# ProPrj_usb__2025-12-10-17-32-04.net
KiCad netlist of a schematic drawn in EasyEDA Pro
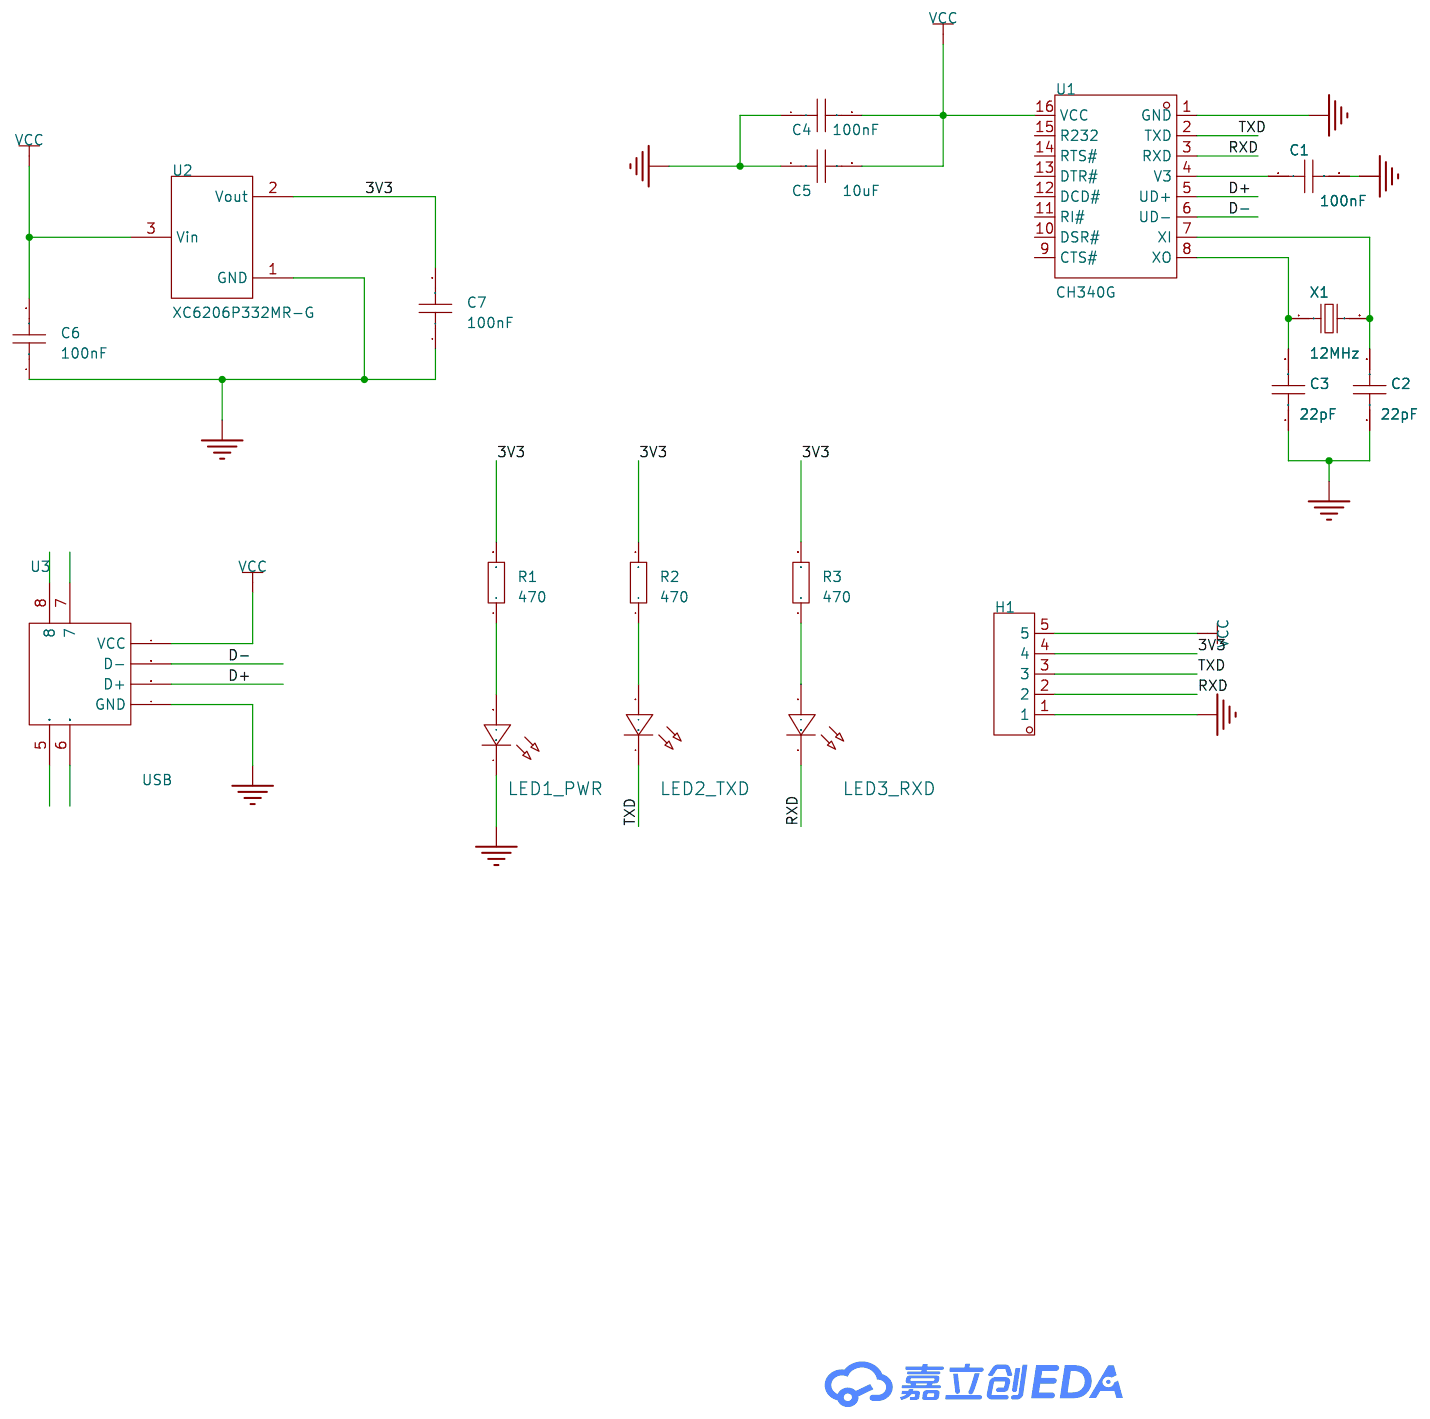
[diagram p0: schematic sheet]

(export (version "E")
  (design (tool "Eeschema 10.0.6"))
  (components
    (comp (ref "C1")
      (value "100nF")
      (footprint "easyedapro:C0603")
      (libsource (lib "easyedapro") (part "Capacitance"))
    )
    (comp (ref "C2")
      (value "22pF")
      (footprint "easyedapro:C0603")
      (libsource (lib "easyedapro") (part "Capacitance"))
    )
    (comp (ref "C3")
      (value "22pF")
      (footprint "easyedapro:C0603")
      (libsource (lib "easyedapro") (part "Capacitance"))
    )
    (comp (ref "C4")
      (value "100nF")
      (footprint "easyedapro:C0603")
      (libsource (lib "easyedapro") (part "Capacitance"))
    )
    (comp (ref "C5")
      (value "10uF")
      (footprint "easyedapro:C0603")
      (libsource (lib "easyedapro") (part "Capacitance"))
    )
    (comp (ref "C6")
      (value "100nF")
      (footprint "easyedapro:C0603")
      (libsource (lib "easyedapro") (part "Capacitance"))
    )
    (comp (ref "C7")
      (value "100nF")
      (footprint "easyedapro:C0603")
      (libsource (lib "easyedapro") (part "Capacitance"))
    )
    (comp (ref "H1")
      (value "~")
      (footprint "easyedapro:HDR-TH_5P-P2.54-V-M")
      (libsource (lib "easyedapro") (part "MTP125-1105S1"))
    )
    (comp (ref "LED1_PWR")
      (value "~")
      (footprint "easyedapro:LED_0603")
      (libsource (lib "easyedapro") (part "LED_R"))
    )
    (comp (ref "LED2_TXD")
      (value "~")
      (footprint "easyedapro:LED_0603")
      (libsource (lib "easyedapro") (part "LED_R"))
    )
    (comp (ref "LED3_RXD")
      (value "~")
      (footprint "easyedapro:LED_0603")
      (libsource (lib "easyedapro") (part "LED_R"))
    )
    (comp (ref "R1") (value "470") (footprint "easyedapro:R0603") (libsource (lib "easyedapro") (part "电阻")))
    (comp (ref "R2") (value "470") (footprint "easyedapro:R0603") (libsource (lib "easyedapro") (part "电阻")))
    (comp (ref "R3") (value "470") (footprint "easyedapro:R0603") (libsource (lib "easyedapro") (part "电阻")))
    (comp (ref "U1")
      (value "CH340G")
      (footprint "easyedapro:SOIC-16_L9.9-W3.9-P1.27-LS6.0-BL")
      (description "应用功能:USB转UART;接口协议:USB 2.0;数据速率:2Mbps;")
      (fields (field (name "Manufacturer") "WCH(南京沁恒)"))
      (libsource (lib "easyedapro") (part "CH340G"))
    )
    (comp (ref "U2")
      (value "XC6206P332MR-G")
      (footprint "easyedapro:SOT-23-3_L2.9-W1.6-P1.90-LS2.8-BR")
      (description "输出类型:固定;工作电压:6V;输出电压:3.3V;输出电流:200mA;电源纹波抑制比(PSRR):-;输出极性:正极;")
      (fields (field (name "Manufacturer") "TOREX(特瑞仕)"))
      (libsource (lib "easyedapro") (part "XC6206P332MR"))
    )
    (comp (ref "U3")
      (value "USB")
      (footprint "easyedapro:USB-SMD_USB_1")
      (libsource (lib "easyedapro") (part "USB"))
    )
    (comp (ref "X1")
      (value "12MHz")
      (footprint "easyedapro:CRYSTAL-SMD_L5.0-W3.2")
      (description "晶振类型:贴片晶振;频率:12MHz;常温频差:±20ppm;负载电容:20pF;频率稳定度:±30ppm;")
      (fields
        (field (name "Manufacturer Part") "XC53G2-12.000-F20LJDT")
        (field (name "Manufacturer") "HCI(杭晶)")
      )
      (libsource (lib "easyedapro") (part "XC53G2-12.000-F20LJDT"))
    )
  )
  (nets
    (net (code "1") (name "/3V3") (class "Default")
      (node (ref "C7") (pin "2") (pinfunction "2_2") (pintype "input"))
      (node (ref "H1") (pin "4") (pinfunction "4_4") (pintype "unspecified"))
      (node (ref "R1") (pin "2") (pinfunction "2_2") (pintype "input"))
      (node (ref "R2") (pin "2") (pinfunction "2_2") (pintype "input"))
      (node (ref "R3") (pin "2") (pinfunction "2_2") (pintype "input"))
      (node (ref "U2") (pin "2") (pinfunction "Vout_2") (pintype "unspecified"))
    )
    (net (code "2") (name "/D+") (class "Default")
      (node (ref "U1") (pin "5") (pinfunction "UD+_5") (pintype "unspecified"))
      (node (ref "U3") (pin "3") (pinfunction "D+_3") (pintype "input"))
    )
    (net (code "3") (name "/D-") (class "Default")
      (node (ref "U1") (pin "6") (pinfunction "UD-_6") (pintype "unspecified"))
      (node (ref "U3") (pin "2") (pinfunction "D-_2") (pintype "input"))
    )
    (net (code "4") (name "/RXD") (class "Default")
      (node (ref "H1") (pin "2") (pinfunction "2_2") (pintype "unspecified"))
      (node (ref "LED3_RXD") (pin "1") (pinfunction "C_1") (pintype "input"))
      (node (ref "U1") (pin "3") (pinfunction "RXD_3") (pintype "unspecified"))
    )
    (net (code "5") (name "/TXD") (class "Default")
      (node (ref "H1") (pin "3") (pinfunction "3_3") (pintype "unspecified"))
      (node (ref "LED2_TXD") (pin "1") (pinfunction "C_1") (pintype "input"))
      (node (ref "U1") (pin "2") (pinfunction "TXD_2") (pintype "unspecified"))
    )
    (net (code "6") (name "GND") (class "Default")
      (node (ref "C1") (pin "2") (pinfunction "2_2") (pintype "input"))
      (node (ref "C2") (pin "1") (pinfunction "1_1") (pintype "input"))
      (node (ref "C3") (pin "1") (pinfunction "1_1") (pintype "input"))
      (node (ref "C4") (pin "1") (pinfunction "1_1") (pintype "input"))
      (node (ref "C5") (pin "1") (pinfunction "1_1") (pintype "input"))
      (node (ref "C6") (pin "1") (pinfunction "1_1") (pintype "input"))
      (node (ref "C7") (pin "1") (pinfunction "1_1") (pintype "input"))
      (node (ref "H1") (pin "1") (pinfunction "1_1") (pintype "unspecified"))
      (node (ref "LED1_PWR") (pin "1") (pinfunction "C_1") (pintype "input"))
      (node (ref "U1") (pin "1") (pinfunction "GND_1") (pintype "unspecified"))
      (node (ref "U2") (pin "1") (pinfunction "GND_1") (pintype "unspecified"))
      (node (ref "U3") (pin "4") (pinfunction "GND_4") (pintype "input"))
    )
    (net (code "7") (name "Net-(LED1_PWR-A)") (class "Default")
      (node (ref "LED1_PWR") (pin "2") (pinfunction "A_2") (pintype "input"))
      (node (ref "R1") (pin "1") (pinfunction "1_1") (pintype "input"))
    )
    (net (code "8") (name "Net-(LED2_TXD-A)") (class "Default")
      (node (ref "LED2_TXD") (pin "2") (pinfunction "A_2") (pintype "input"))
      (node (ref "R2") (pin "1") (pinfunction "1_1") (pintype "input"))
    )
    (net (code "9") (name "Net-(LED3_RXD-A)") (class "Default")
      (node (ref "LED3_RXD") (pin "2") (pinfunction "A_2") (pintype "input"))
      (node (ref "R3") (pin "1") (pinfunction "1_1") (pintype "input"))
    )
    (net (code "10") (name "Net-(U1-V3)") (class "Default")
      (node (ref "C1") (pin "1") (pinfunction "1_1") (pintype "input"))
      (node (ref "U1") (pin "4") (pinfunction "V3_4") (pintype "unspecified"))
    )
    (net (code "11") (name "Net-(U1-XI)") (class "Default")
      (node (ref "C2") (pin "2") (pinfunction "2_2") (pintype "input"))
      (node (ref "U1") (pin "7") (pinfunction "XI_7") (pintype "unspecified"))
      (node (ref "X1") (pin "2") (pinfunction "2_2") (pintype "unspecified"))
    )
    (net (code "12") (name "Net-(U1-XO)") (class "Default")
      (node (ref "C3") (pin "2") (pinfunction "2_2") (pintype "input"))
      (node (ref "U1") (pin "8") (pinfunction "XO_8") (pintype "unspecified"))
      (node (ref "X1") (pin "1") (pinfunction "1_1") (pintype "unspecified"))
    )
    (net (code "13") (name "VCC") (class "Default")
      (node (ref "C4") (pin "2") (pinfunction "2_2") (pintype "input"))
      (node (ref "C5") (pin "2") (pinfunction "2_2") (pintype "input"))
      (node (ref "C6") (pin "2") (pinfunction "2_2") (pintype "input"))
      (node (ref "H1") (pin "5") (pinfunction "5_5") (pintype "unspecified"))
      (node (ref "U1") (pin "16") (pinfunction "VCC_16") (pintype "unspecified"))
      (node (ref "U2") (pin "3") (pinfunction "Vin_3") (pintype "unspecified"))
      (node (ref "U3") (pin "1") (pinfunction "VCC_1") (pintype "input"))
    )
    (net (code "14") (name "unconnected-(U1-CTS#-Pad9)") (class "Default")
      (node (ref "U1") (pin "9") (pinfunction "CTS#_9") (pintype "unspecified"))
    )
    (net (code "15") (name "unconnected-(U1-DCD#-Pad12)") (class "Default")
      (node (ref "U1") (pin "12") (pinfunction "DCD#_12") (pintype "unspecified"))
    )
    (net (code "16") (name "unconnected-(U1-DSR#-Pad10)") (class "Default")
      (node (ref "U1") (pin "10") (pinfunction "DSR#_10") (pintype "unspecified"))
    )
    (net (code "17") (name "unconnected-(U1-DTR#-Pad13)") (class "Default")
      (node (ref "U1") (pin "13") (pinfunction "DTR#_13") (pintype "unspecified"))
    )
    (net (code "18") (name "unconnected-(U1-R232-Pad15)") (class "Default")
      (node (ref "U1") (pin "15") (pinfunction "R232_15") (pintype "unspecified"))
    )
    (net (code "19") (name "unconnected-(U1-RI#-Pad11)") (class "Default")
      (node (ref "U1") (pin "11") (pinfunction "RI#_11") (pintype "unspecified"))
    )
    (net (code "20") (name "unconnected-(U1-RTS#-Pad14)") (class "Default")
      (node (ref "U1") (pin "14") (pinfunction "RTS#_14") (pintype "unspecified"))
    )
    (net (code "21") (name "unconnected-(U3-Pad7)") (class "Default")
      (node (ref "U3") (pin "7") (pinfunction "7_7") (pintype "unspecified"))
    )
    (net (code "22") (name "unconnected-(U3-Pad8)") (class "Default")
      (node (ref "U3") (pin "8") (pinfunction "8_8") (pintype "unspecified"))
    )
    (net (code "23") (name "unconnected-(U3-SH1-Pad5)") (class "Default")
      (node (ref "U3") (pin "5") (pinfunction "SH1_5") (pintype "unspecified"))
    )
    (net (code "24") (name "unconnected-(U3-SH2-Pad6)") (class "Default")
      (node (ref "U3") (pin "6") (pinfunction "SH2_6") (pintype "unspecified"))
    )
  )
)
